# Full_Schematic.net
KiCad netlist of a schematic drawn in EAGLE
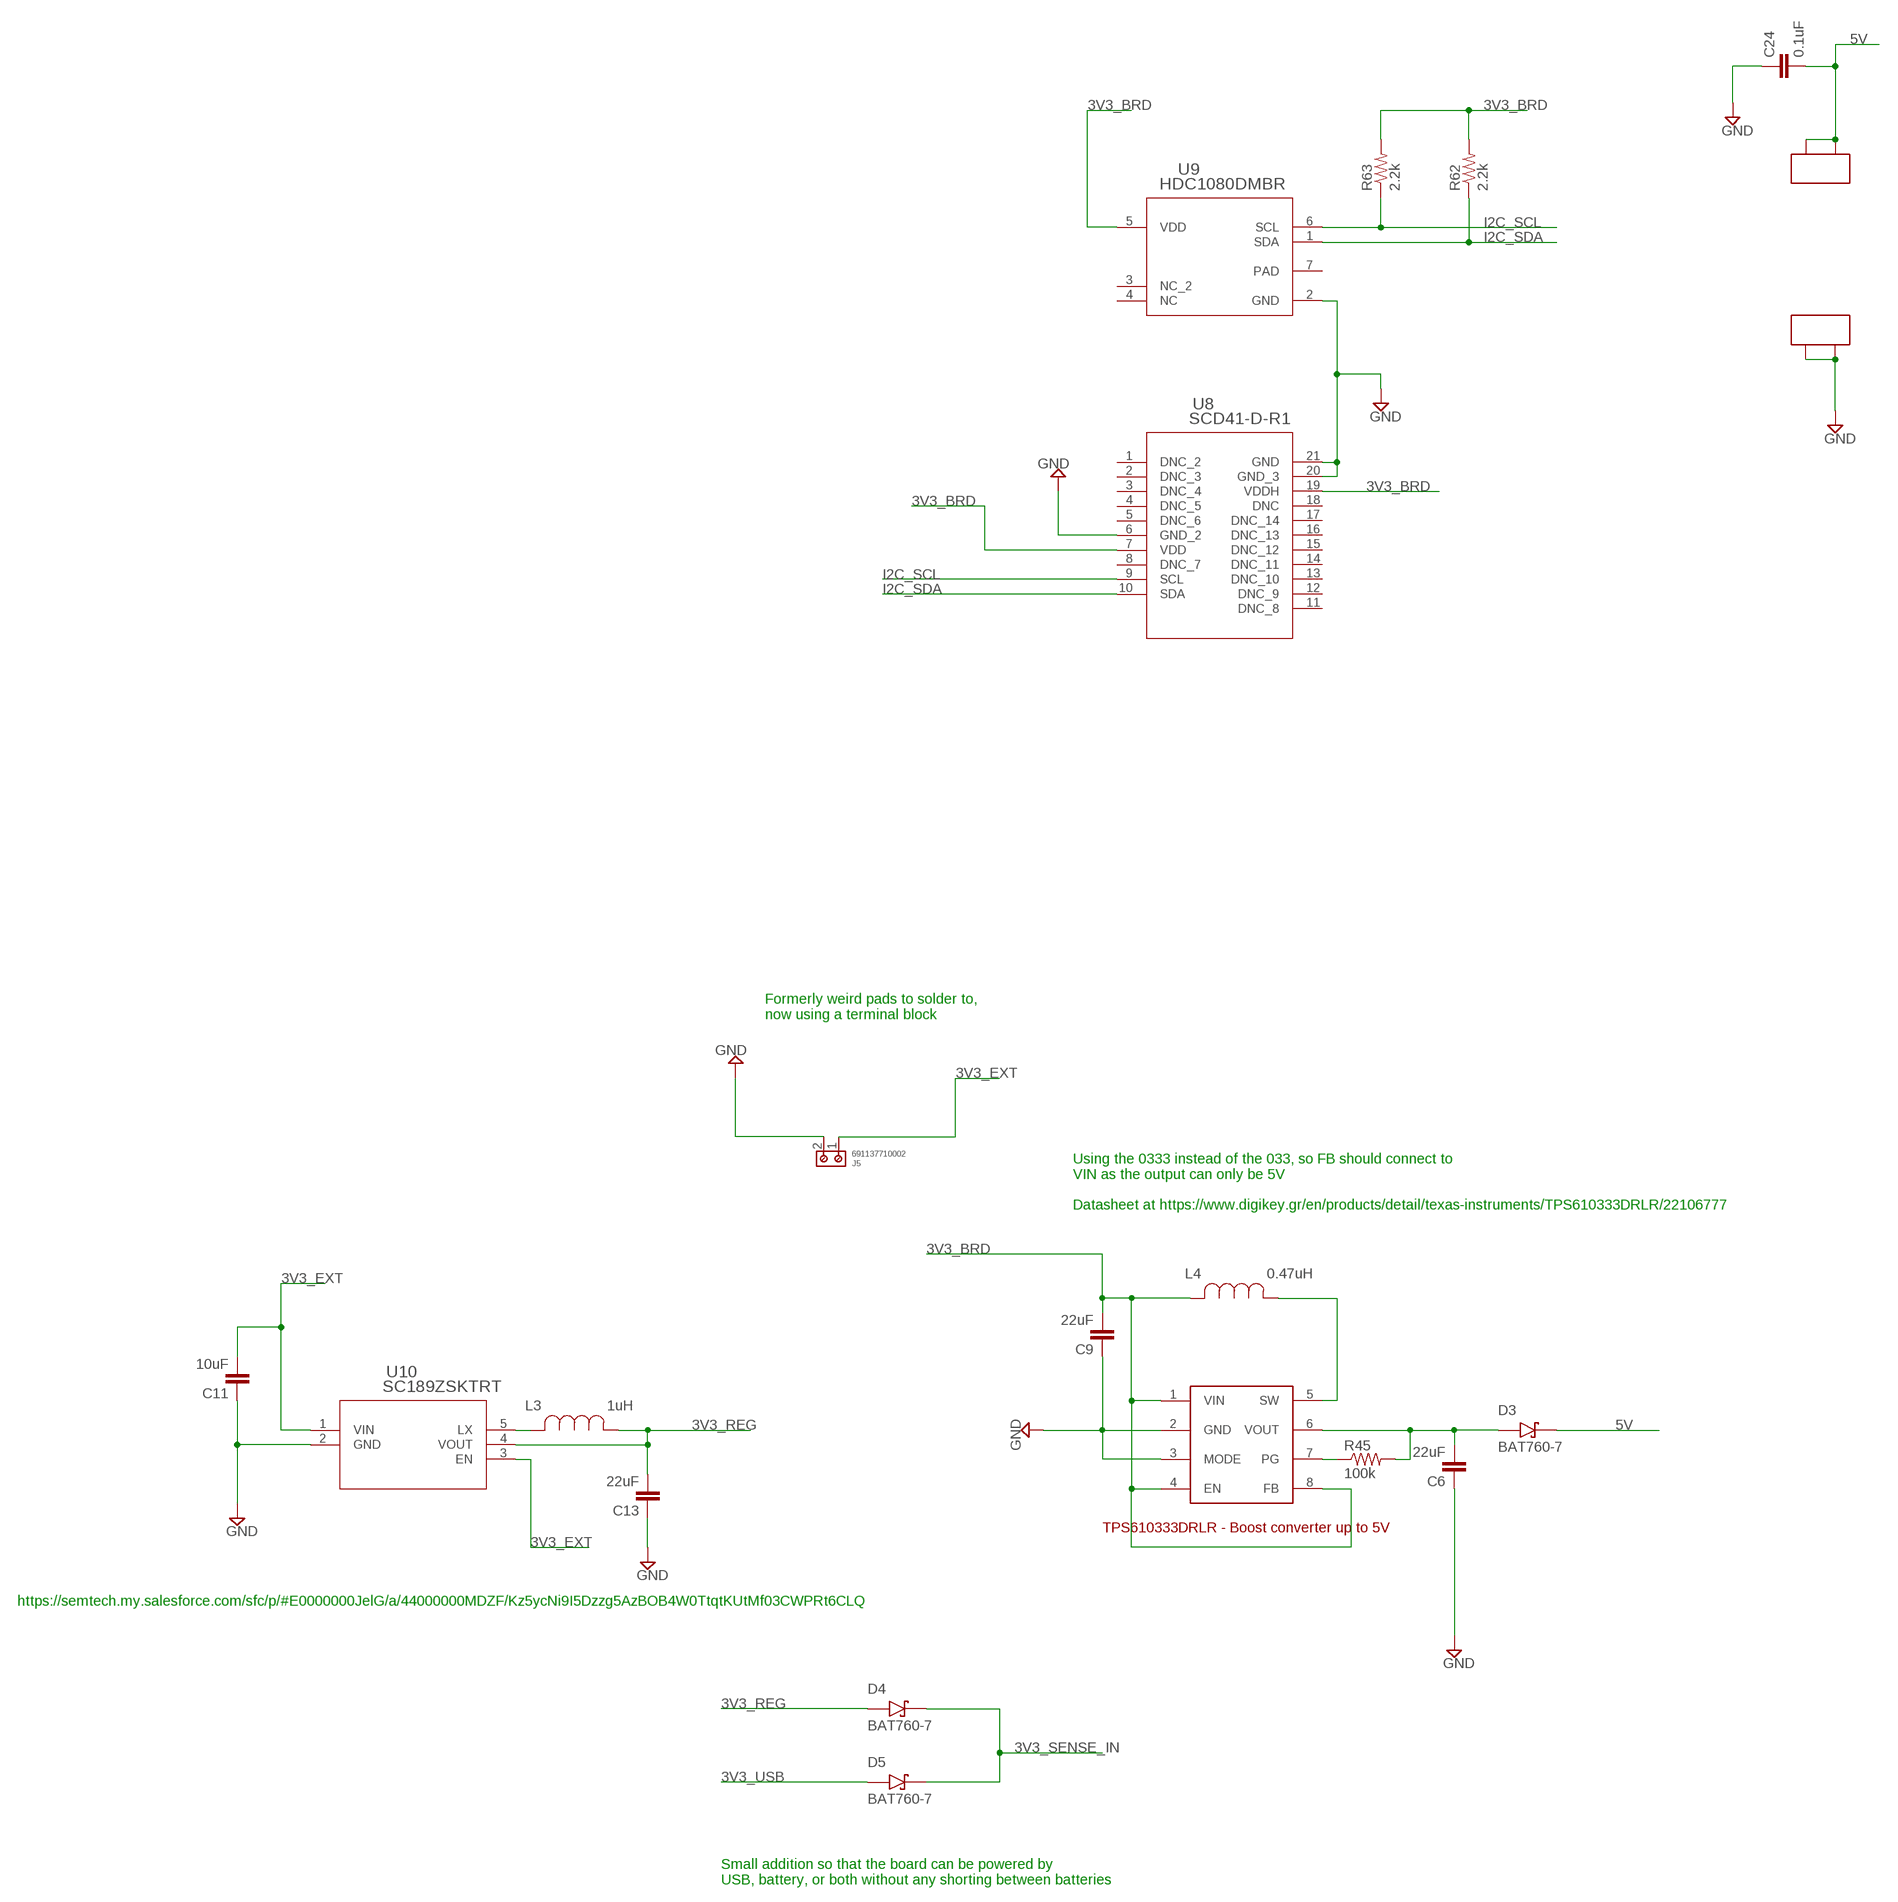
[diagram p0: schematic, sheet 1, part 1 of 3]
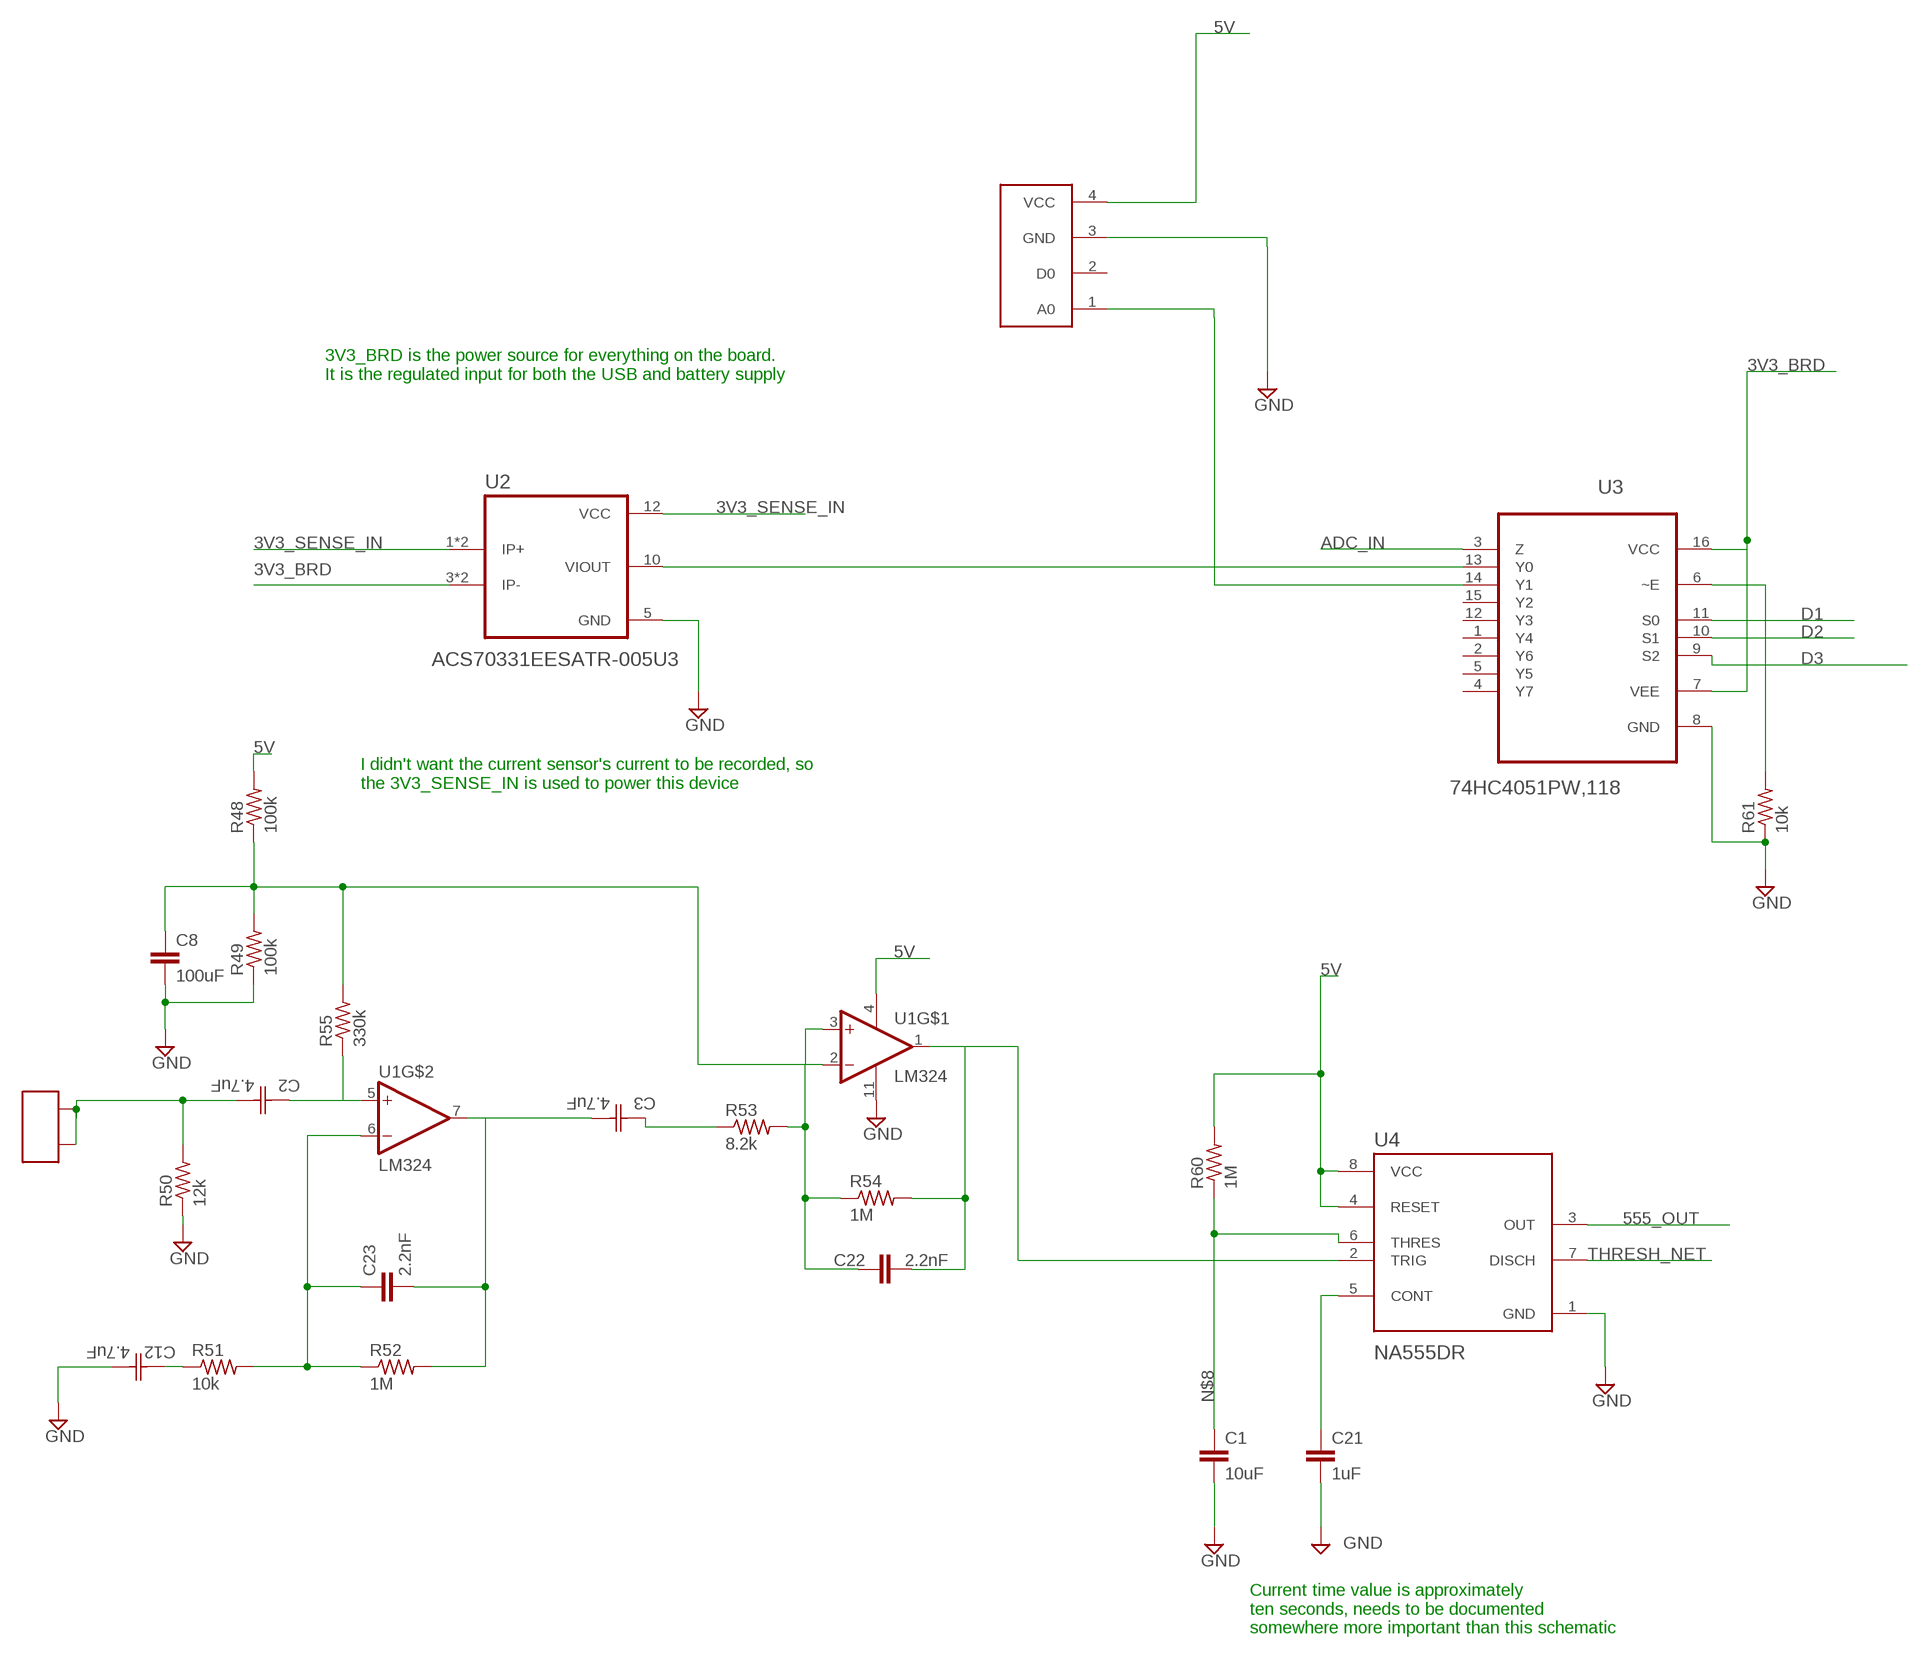
[diagram p1: schematic, sheet 1, part 2 of 3]
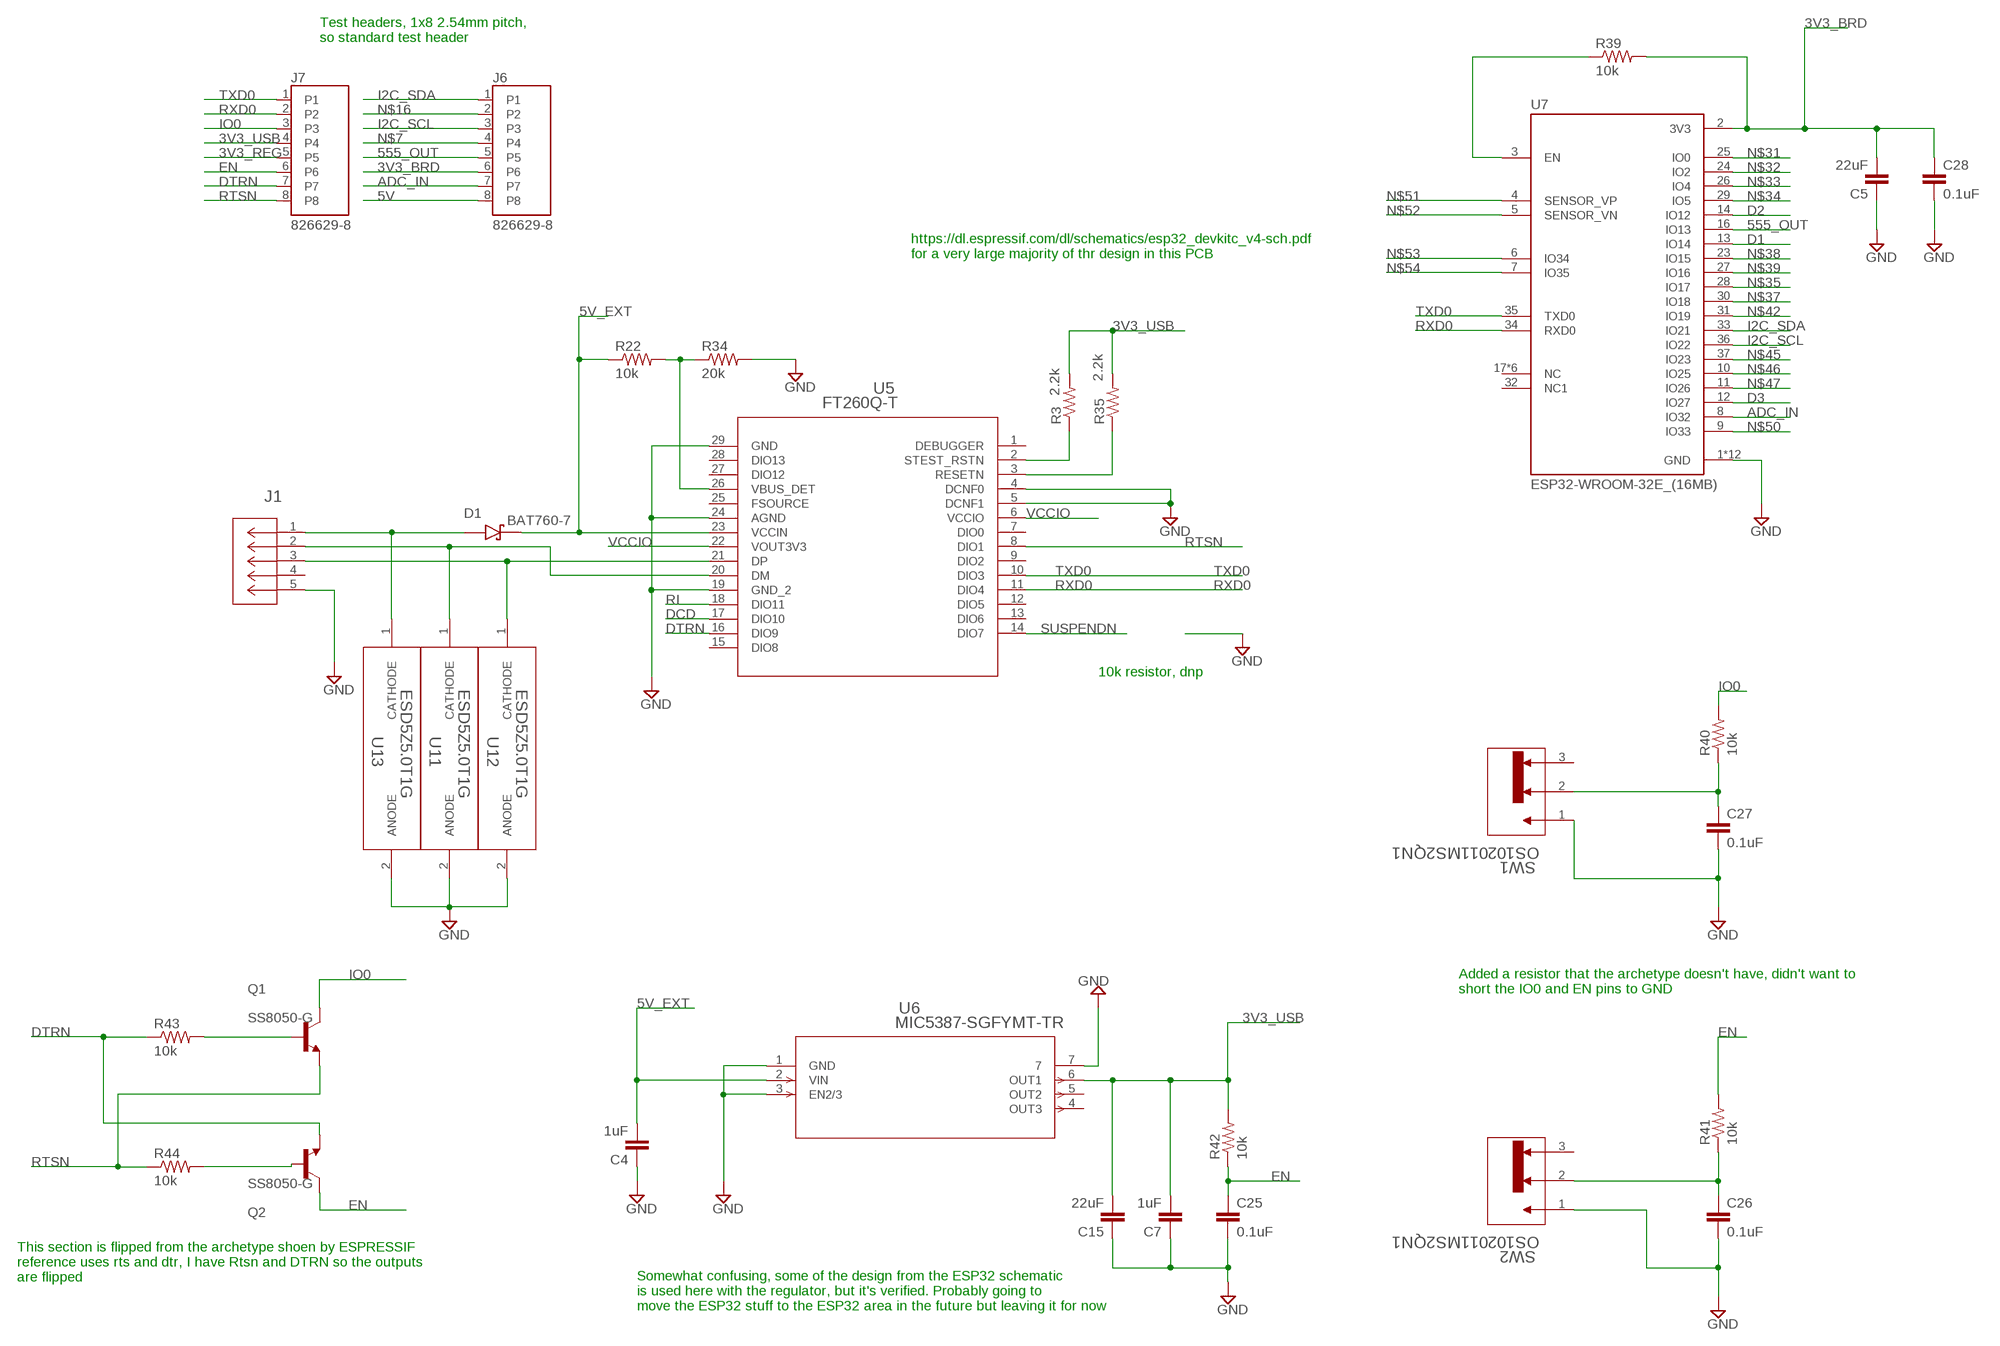
[diagram p2: schematic, sheet 1, part 3 of 3]

(export (version "E")
  (design (tool "Eeschema 10.0.6"))
  (components
    (comp (ref "C1")
      (value "10uF")
      (footprint "eagle-import:C0603")
      (libsource (lib "eagle-import") (part "C-EUC0603"))
    )
    (comp (ref "C2")
      (value "4.7uF")
      (footprint "eagle-import:CAP_WCAP-ATG5_5X11_WRE")
      (fields
        (field (name "MANUFACTURER_PART_NUMBER") "860020472001")
        (field (name "COPYRIGHT") "Copyright (C) 2024 Ultra Librarian. All rights reserved.")
      )
      (libsource (lib "eagle-import") (part "860020472001"))
    )
    (comp (ref "C3")
      (value "4.7uF")
      (footprint "eagle-import:CAP_WCAP-ATG5_5X11_WRE")
      (fields
        (field (name "MANUFACTURER_PART_NUMBER") "860020472001")
        (field (name "COPYRIGHT") "Copyright (C) 2024 Ultra Librarian. All rights reserved.")
      )
      (libsource (lib "eagle-import") (part "860020472001"))
    )
    (comp (ref "C4")
      (value "1uF")
      (footprint "eagle-import:C0603")
      (libsource (lib "eagle-import") (part "C-EUC0603"))
    )
    (comp (ref "C5")
      (value "22uF")
      (footprint "eagle-import:C0603")
      (libsource (lib "eagle-import") (part "C-EUC0603"))
    )
    (comp (ref "C6")
      (value "22uF")
      (footprint "eagle-import:C0603")
      (libsource (lib "eagle-import") (part "C-EUC0603"))
    )
    (comp (ref "C7")
      (value "1uF")
      (footprint "eagle-import:C0603")
      (libsource (lib "eagle-import") (part "C-EUC0603"))
    )
    (comp (ref "C8")
      (value "100uF")
      (footprint "eagle-import:C1206")
      (libsource (lib "eagle-import") (part "C-EUC1206"))
    )
    (comp (ref "C9")
      (value "22uF")
      (footprint "eagle-import:C0603")
      (libsource (lib "eagle-import") (part "C-EUC0603"))
    )
    (comp (ref "C11")
      (value "10uF")
      (footprint "eagle-import:C0603")
      (libsource (lib "eagle-import") (part "C-EUC0603"))
    )
    (comp (ref "C12")
      (value "4.7uF")
      (footprint "eagle-import:CAP_WCAP-ATG5_5X11_WRE")
      (fields
        (field (name "MANUFACTURER_PART_NUMBER") "860020472001")
        (field (name "COPYRIGHT") "Copyright (C) 2024 Ultra Librarian. All rights reserved.")
      )
      (libsource (lib "eagle-import") (part "860020472001"))
    )
    (comp (ref "C13")
      (value "22uF")
      (footprint "eagle-import:C0603")
      (libsource (lib "eagle-import") (part "C-EUC0603"))
    )
    (comp (ref "C15")
      (value "22uF")
      (footprint "eagle-import:C0603")
      (libsource (lib "eagle-import") (part "C-EUC0603"))
    )
    (comp (ref "C21")
      (value "1uF")
      (footprint "eagle-import:C0402")
      (libsource (lib "eagle-import") (part "C-EUC0402"))
    )
    (comp (ref "C22")
      (value "2.2nF")
      (footprint "eagle-import:C0402")
      (libsource (lib "eagle-import") (part "C-EUC0402"))
    )
    (comp (ref "C23")
      (value "2.2nF")
      (footprint "eagle-import:C0402")
      (libsource (lib "eagle-import") (part "C-EUC0402"))
    )
    (comp (ref "C24")
      (value "0.1uF")
      (footprint "eagle-import:C0402")
      (libsource (lib "eagle-import") (part "C-EUC0402"))
    )
    (comp (ref "C25")
      (value "0.1uF")
      (footprint "eagle-import:C0402")
      (libsource (lib "eagle-import") (part "C-EUC0402"))
    )
    (comp (ref "C26")
      (value "0.1uF")
      (footprint "eagle-import:C0402")
      (libsource (lib "eagle-import") (part "C-EUC0402"))
    )
    (comp (ref "C27")
      (value "0.1uF")
      (footprint "eagle-import:C0402")
      (libsource (lib "eagle-import") (part "C-EUC0402"))
    )
    (comp (ref "C28")
      (value "0.1uF")
      (footprint "eagle-import:C0402")
      (libsource (lib "eagle-import") (part "C-EUC0402"))
    )
    (comp (ref "D1")
      (value "BAT760-7")
      (footprint "eagle-import:SOD2513X120N")
      (fields (field (name "MANUFACTURER") "DIODES"))
      (libsource (lib "eagle-import") (part "BAT760-7"))
    )
    (comp (ref "D3")
      (value "BAT760-7")
      (footprint "eagle-import:SOD2513X120N")
      (fields (field (name "MANUFACTURER") "DIODES"))
      (libsource (lib "eagle-import") (part "BAT760-7"))
    )
    (comp (ref "D4")
      (value "BAT760-7")
      (footprint "eagle-import:SOD2513X120N")
      (fields (field (name "MANUFACTURER") "DIODES"))
      (libsource (lib "eagle-import") (part "BAT760-7"))
    )
    (comp (ref "D5")
      (value "BAT760-7")
      (footprint "eagle-import:SOD2513X120N")
      (fields (field (name "MANUFACTURER") "DIODES"))
      (libsource (lib "eagle-import") (part "BAT760-7"))
    )
    (comp (ref "J1")
      (value "10118193-0001LF")
      (footprint "eagle-import:CONN_10118193-0001LF_AMP")
      (fields (field (name "COPYRIGHT") "Copyright (C) 2024 Ultra Librarian. All rights reserved."))
      (libsource (lib "eagle-import") (part "10118193-0001LF"))
    )
    (comp (ref "J5")
      (value "691137710002")
      (footprint "eagle-import:691137710002")
      (fields (field (name "MF") "Wurth Electronics"))
      (libsource (lib "eagle-import") (part "691137710002"))
    )
    (comp (ref "J6")
      (value "826629-8")
      (footprint "eagle-import:TE_826629-8")
      (fields (field (name "MF") "TE Connectivity"))
      (libsource (lib "eagle-import") (part "826629-8"))
    )
    (comp (ref "J7")
      (value "826629-8")
      (footprint "eagle-import:TE_826629-8")
      (fields (field (name "MF") "TE Connectivity"))
      (libsource (lib "eagle-import") (part "826629-8"))
    )
    (comp (ref "L3")
      (value "1uH")
      (footprint "eagle-import:DFE252012P-1R0M=P2")
      (fields
        (field (name "MANUFACTURER_PART_NUMBER") "DFE252012P-1R0M=P2")
        (field (name "COPYRIGHT") "Copyright (C) 2024 Ultra Librarian. All rights reserved.")
      )
      (libsource (lib "eagle-import") (part "DFE252012P-1R0M=P2"))
    )
    (comp (ref "L4")
      (value "0.47uH")
      (footprint "eagle-import:DFE252012P-1R0M=P2")
      (fields
        (field (name "MANUFACTURER_PART_NUMBER") "DFE252012P-1R0M=P2")
        (field (name "COPYRIGHT") "Copyright (C) 2024 Ultra Librarian. All rights reserved.")
      )
      (libsource (lib "eagle-import") (part "DFE252012P-1R0M=P2"))
    )
    (comp (ref "Q1")
      (value "SS8050-G")
      (footprint "eagle-import:TRANS_SS8050-G")
      (fields (field (name "MANUFACTURER") "Comchip"))
      (libsource (lib "eagle-import") (part "SS8050-G"))
    )
    (comp (ref "Q2")
      (value "SS8050-G")
      (footprint "eagle-import:TRANS_SS8050-G")
      (fields (field (name "MANUFACTURER") "Comchip"))
      (libsource (lib "eagle-import") (part "SS8050-G"))
    )
    (comp (ref "R3")
      (value "2.2k")
      (footprint "eagle-import:R0402")
      (libsource (lib "eagle-import") (part "R-US_R0402"))
    )
    (comp (ref "R22")
      (value "10k")
      (footprint "eagle-import:R0402")
      (libsource (lib "eagle-import") (part "R-US_R0402"))
    )
    (comp (ref "R34")
      (value "20k")
      (footprint "eagle-import:R0402")
      (libsource (lib "eagle-import") (part "R-US_R0402"))
    )
    (comp (ref "R35")
      (value "2.2k")
      (footprint "eagle-import:R0402")
      (libsource (lib "eagle-import") (part "R-US_R0402"))
    )
    (comp (ref "R39")
      (value "10k")
      (footprint "eagle-import:R0402")
      (libsource (lib "eagle-import") (part "R-US_R0402"))
    )
    (comp (ref "R40")
      (value "10k")
      (footprint "eagle-import:R0402")
      (libsource (lib "eagle-import") (part "R-US_R0402"))
    )
    (comp (ref "R41")
      (value "10k")
      (footprint "eagle-import:R0402")
      (libsource (lib "eagle-import") (part "R-US_R0402"))
    )
    (comp (ref "R42")
      (value "10k")
      (footprint "eagle-import:R0402")
      (libsource (lib "eagle-import") (part "R-US_R0402"))
    )
    (comp (ref "R43")
      (value "10k")
      (footprint "eagle-import:R0402")
      (libsource (lib "eagle-import") (part "R-US_R0402"))
    )
    (comp (ref "R44")
      (value "10k")
      (footprint "eagle-import:R0402")
      (libsource (lib "eagle-import") (part "R-US_R0402"))
    )
    (comp (ref "R45")
      (value "100k")
      (footprint "eagle-import:R0402")
      (libsource (lib "eagle-import") (part "R-US_R0402"))
    )
    (comp (ref "R48")
      (value "100k")
      (footprint "eagle-import:R0402")
      (libsource (lib "eagle-import") (part "R-US_R0402"))
    )
    (comp (ref "R49")
      (value "100k")
      (footprint "eagle-import:R0402")
      (libsource (lib "eagle-import") (part "R-US_R0402"))
    )
    (comp (ref "R50")
      (value "12k")
      (footprint "eagle-import:R0402")
      (libsource (lib "eagle-import") (part "R-US_R0402"))
    )
    (comp (ref "R51")
      (value "10k")
      (footprint "eagle-import:R0402")
      (libsource (lib "eagle-import") (part "R-US_R0402"))
    )
    (comp (ref "R52")
      (value "1M")
      (footprint "eagle-import:R0402")
      (libsource (lib "eagle-import") (part "R-US_R0402"))
    )
    (comp (ref "R53")
      (value "8.2k")
      (footprint "eagle-import:R0402")
      (libsource (lib "eagle-import") (part "R-US_R0402"))
    )
    (comp (ref "R54")
      (value "1M")
      (footprint "eagle-import:R0402")
      (libsource (lib "eagle-import") (part "R-US_R0402"))
    )
    (comp (ref "R55")
      (value "330k")
      (footprint "eagle-import:R0402")
      (libsource (lib "eagle-import") (part "R-US_R0402"))
    )
    (comp (ref "R60")
      (value "1M")
      (footprint "eagle-import:R0402")
      (libsource (lib "eagle-import") (part "R-US_R0402"))
    )
    (comp (ref "R61")
      (value "10k")
      (footprint "eagle-import:R0402")
      (libsource (lib "eagle-import") (part "R-US_R0402"))
    )
    (comp (ref "R62")
      (value "2.2k")
      (footprint "eagle-import:R0402")
      (libsource (lib "eagle-import") (part "R-US_R0402"))
    )
    (comp (ref "R63")
      (value "2.2k")
      (footprint "eagle-import:R0402")
      (libsource (lib "eagle-import") (part "R-US_R0402"))
    )
    (comp (ref "SW1")
      (value "OS102011MS2QN1")
      (footprint "eagle-import:SPDT_OS102011_CNK")
      (fields (field (name "COPYRIGHT") "Copyright (C) 2024 Ultra Librarian. All rights reserved."))
      (libsource (lib "eagle-import") (part "OS102011MS2QN1"))
    )
    (comp (ref "SW2")
      (value "OS102011MS2QN1")
      (footprint "eagle-import:SPDT_OS102011_CNK")
      (fields (field (name "COPYRIGHT") "Copyright (C) 2024 Ultra Librarian. All rights reserved."))
      (libsource (lib "eagle-import") (part "OS102011MS2QN1"))
    )
    (comp (ref "U$1")
      (value "2PIN_HEADER")
      (footprint "eagle-import:2PIN_HEADER")
      (libsource (lib "eagle-import") (part "2PIN_HEADER"))
    )
    (comp (ref "U$2")
      (value "2PIN_HEADER")
      (footprint "eagle-import:2PIN_HEADER")
      (libsource (lib "eagle-import") (part "2PIN_HEADER"))
    )
    (comp (ref "U$3")
      (value "MQ_7")
      (footprint "eagle-import:MQ-7")
      (libsource (lib "eagle-import") (part "MQ_7"))
    )
    (comp (ref "U$4")
      (value "TPS610333DRLR")
      (footprint "eagle-import:TPS610333DRLR")
      (libsource (lib "eagle-import") (part "TPS610333DRLR"))
    )
    (comp (ref "U$5")
      (value "2PIN_HEADER")
      (footprint "eagle-import:2PIN_HEADER")
      (libsource (lib "eagle-import") (part "2PIN_HEADER"))
    )
    (comp (ref "U1")
      (value "LM324")
      (footprint "eagle-import:SOIC127P600X175-14N")
      (fields (field (name "MF") "Intersil") (field (name "MP") "LM324.."))
      (libsource (lib "eagle-import") (part "LM324"))
    )
    (comp (ref "U2")
      (value "ACS70331EESATR-005U3")
      (footprint "eagle-import:ALLEGRO_ACS70331EESATR-005U3")
      (fields (field (name "MF") "Allegro MicroSystems LLC"))
      (libsource (lib "eagle-import") (part "ACS70331EESATR-005U3"))
    )
    (comp (ref "U3")
      (value "74HC4051PW,118")
      (footprint "eagle-import:SOP65P640X110-16N")
      (fields (field (name "MF") "Nexperia USA Inc."))
      (libsource (lib "eagle-import") (part "74HC4051PW,118"))
    )
    (comp (ref "U4")
      (value "NA555DR")
      (footprint "eagle-import:SOIC127P599X175-8N")
      (fields (field (name "MANUFACTURER") "Texas Instruments"))
      (libsource (lib "eagle-import") (part "NA555DR"))
    )
    (comp (ref "U5")
      (value "FT260Q-T")
      (footprint "eagle-import:WQFN-28_FTD")
      (fields (field (name "COPYRIGHT") "Copyright (C) 2024 Ultra Librarian. All rights reserved."))
      (libsource (lib "eagle-import") (part "FT260Q-T"))
    )
    (comp (ref "U6")
      (value "MIC5387-SGFYMT-TR")
      (footprint "eagle-import:MLF-6_MT_MCH")
      (fields (field (name "COPYRIGHT") "Copyright (C) 2024 Ultra Librarian. All rights reserved."))
      (libsource (lib "eagle-import") (part "MIC5387-SGFYMT-TR"))
    )
    (comp (ref "U7")
      (value "ESP32-WROOM-32E_(16MB)")
      (footprint "eagle-import:XCVR_ESP32-WROOM-32E_(16MB)")
      (fields (field (name "MF") "Espressif Systems") (field (name "MP") "ESP32-WROOM-32E (16MB)"))
      (libsource (lib "eagle-import") (part "ESP32-WROOM-32E_(16MB)"))
    )
    (comp (ref "U8")
      (value "SCD41-D-R1")
      (footprint "eagle-import:SCD41-D-R1_SEN")
      (fields (field (name "COPYRIGHT") "Copyright (C) 2024 Ultra Librarian. All rights reserved."))
      (libsource (lib "eagle-import") (part "SCD41-D-R1"))
    )
    (comp (ref "U9")
      (value "HDC1080DMBR")
      (footprint "eagle-import:DMB0006A")
      (fields (field (name "COPYRIGHT") "Copyright (C) 2024 Ultra Librarian. All rights reserved."))
      (libsource (lib "eagle-import") (part "HDC1080DMBR"))
    )
    (comp (ref "U10")
      (value "SC189ZSKTRT")
      (footprint "eagle-import:SOT23-5-SC189_SEM")
      (fields (field (name "COPYRIGHT") "Copyright (C) 2024 Ultra Librarian. All rights reserved."))
      (libsource (lib "eagle-import") (part "SC189ZSKTRT"))
    )
    (comp (ref "U11")
      (value "ESD5Z5.0T1G")
      (footprint "eagle-import:SOD-523_0P9X1P3_ONS")
      (fields (field (name "COPYRIGHT") "Copyright (C) 2024 Ultra Librarian. All rights reserved."))
      (libsource (lib "eagle-import") (part "ESD5Z5.0T1G"))
    )
    (comp (ref "U12")
      (value "ESD5Z5.0T1G")
      (footprint "eagle-import:SOD-523_0P9X1P3_ONS")
      (fields (field (name "COPYRIGHT") "Copyright (C) 2024 Ultra Librarian. All rights reserved."))
      (libsource (lib "eagle-import") (part "ESD5Z5.0T1G"))
    )
    (comp (ref "U13")
      (value "ESD5Z5.0T1G")
      (footprint "eagle-import:SOD-523_0P9X1P3_ONS")
      (fields (field (name "COPYRIGHT") "Copyright (C) 2024 Ultra Librarian. All rights reserved."))
      (libsource (lib "eagle-import") (part "ESD5Z5.0T1G"))
    )
  )
  (nets
    (net (code "1") (name "/3V3_BRD") (class "Default")
      (node (ref "C28") (pin "1") (pinfunction "1_1") (pintype "passive"))
      (node (ref "C5") (pin "2") (pinfunction "2_2") (pintype "passive"))
      (node (ref "C9") (pin "2") (pinfunction "2_2") (pintype "passive"))
      (node (ref "J6") (pin "6") (pinfunction "P6_6") (pintype "passive"))
      (node (ref "L4") (pin "2") (pinfunction "2_2") (pintype "passive"))
      (node (ref "R39") (pin "2") (pinfunction "2_2") (pintype "passive"))
      (node (ref "R62") (pin "2") (pinfunction "2_2") (pintype "passive"))
      (node (ref "R63") (pin "2") (pinfunction "2_2") (pintype "passive"))
      (node (ref "U$4") (pin "1") (pinfunction "VIN_1") (pintype "bidirectional"))
      (node (ref "U$4") (pin "4") (pinfunction "EN_4") (pintype "bidirectional"))
      (node (ref "U$4") (pin "8") (pinfunction "FB_8") (pintype "bidirectional"))
      (node (ref "U2") (pin "3") (pinfunction "IP-_3") (pintype "input"))
      (node (ref "U2") (pin "4") (pinfunction "IP-_4") (pintype "input"))
      (node (ref "U3") (pin "16") (pinfunction "VCC_16") (pintype "power_in"))
      (node (ref "U3") (pin "7") (pinfunction "VEE_7") (pintype "power_in"))
      (node (ref "U7") (pin "2") (pinfunction "3V3_2") (pintype "power_in"))
      (node (ref "U8") (pin "19") (pinfunction "VDDH_19") (pintype "power_in"))
      (node (ref "U8") (pin "7") (pinfunction "VDD_7") (pintype "power_in"))
      (node (ref "U9") (pin "5") (pinfunction "VDD_5") (pintype "power_in"))
    )
    (net (code "2") (name "/3V3_EXT") (class "Default")
      (node (ref "C11") (pin "2") (pinfunction "2_2") (pintype "passive"))
      (node (ref "J5") (pin "1") (pinfunction "1_1") (pintype "passive"))
      (node (ref "U10") (pin "1") (pinfunction "VIN_1") (pintype "power_in"))
      (node (ref "U10") (pin "3") (pinfunction "EN_3") (pintype "passive"))
    )
    (net (code "3") (name "/3V3_REG") (class "Default")
      (node (ref "C13") (pin "2") (pinfunction "2_2") (pintype "passive"))
      (node (ref "D4") (pin "A") (pinfunction "A_A") (pintype "passive"))
      (node (ref "J7") (pin "5") (pinfunction "P5_5") (pintype "passive"))
      (node (ref "L3") (pin "1") (pinfunction "1_1") (pintype "passive"))
      (node (ref "U10") (pin "4") (pinfunction "VOUT_4") (pintype "output"))
    )
    (net (code "4") (name "/3V3_SENSE_IN") (class "Default")
      (node (ref "D4") (pin "C") (pinfunction "K_C") (pintype "passive"))
      (node (ref "D5") (pin "C") (pinfunction "K_C") (pintype "passive"))
      (node (ref "U2") (pin "1") (pinfunction "IP+_1") (pintype "input"))
      (node (ref "U2") (pin "12") (pinfunction "VCC_12") (pintype "power_in"))
      (node (ref "U2") (pin "2") (pinfunction "IP+_2") (pintype "input"))
    )
    (net (code "5") (name "/3V3_USB") (class "Default")
      (node (ref "C15") (pin "2") (pinfunction "2_2") (pintype "passive"))
      (node (ref "C7") (pin "2") (pinfunction "2_2") (pintype "passive"))
      (node (ref "D5") (pin "A") (pinfunction "A_A") (pintype "passive"))
      (node (ref "J7") (pin "4") (pinfunction "P4_4") (pintype "passive"))
      (node (ref "R3") (pin "2") (pinfunction "2_2") (pintype "passive"))
      (node (ref "R35") (pin "2") (pinfunction "2_2") (pintype "passive"))
      (node (ref "R42") (pin "2") (pinfunction "2_2") (pintype "passive"))
      (node (ref "U6") (pin "6") (pinfunction "OUT1_6") (pintype "output"))
    )
    (net (code "6") (name "/5V") (class "Default")
      (node (ref "C24") (pin "2") (pinfunction "2_2") (pintype "passive"))
      (node (ref "D3") (pin "C") (pinfunction "K_C") (pintype "passive"))
      (node (ref "J6") (pin "8") (pinfunction "P8_8") (pintype "passive"))
      (node (ref "R48") (pin "2") (pinfunction "2_2") (pintype "passive"))
      (node (ref "R60") (pin "2") (pinfunction "2_2") (pintype "passive"))
      (node (ref "U$2") (pin "1") (pinfunction "1_1") (pintype "passive"))
      (node (ref "U$2") (pin "2") (pinfunction "2_2") (pintype "passive"))
      (node (ref "U$3") (pin "4") (pinfunction "VCC_4") (pintype "bidirectional"))
      (node (ref "U1") (pin "4") (pinfunction "VCC+_4") (pintype "power_in"))
      (node (ref "U4") (pin "4") (pinfunction "RESET_4") (pintype "input"))
      (node (ref "U4") (pin "8") (pinfunction "VCC_8") (pintype "power_in"))
    )
    (net (code "7") (name "/5V_EXT") (class "Default")
      (node (ref "C4") (pin "2") (pinfunction "2_2") (pintype "passive"))
      (node (ref "D1") (pin "C") (pinfunction "K_C") (pintype "passive"))
      (node (ref "R22") (pin "1") (pinfunction "1_1") (pintype "passive"))
      (node (ref "U5") (pin "23") (pinfunction "VCCIN_23") (pintype "power_in"))
      (node (ref "U6") (pin "2") (pinfunction "VIN_2") (pintype "input"))
    )
    (net (code "8") (name "/555_OUT") (class "Default")
      (node (ref "J6") (pin "5") (pinfunction "P5_5") (pintype "passive"))
      (node (ref "U4") (pin "3") (pinfunction "OUT_3") (pintype "output"))
      (node (ref "U7") (pin "16") (pinfunction "IO13_16") (pintype "bidirectional"))
    )
    (net (code "9") (name "/ADC_IN") (class "Default")
      (node (ref "J6") (pin "7") (pinfunction "P7_7") (pintype "passive"))
      (node (ref "U3") (pin "3") (pinfunction "Z_3") (pintype "bidirectional"))
      (node (ref "U7") (pin "8") (pinfunction "IO32_8") (pintype "bidirectional"))
    )
    (net (code "10") (name "/D1") (class "Default")
      (node (ref "U3") (pin "11") (pinfunction "S0_11") (pintype "input"))
      (node (ref "U7") (pin "13") (pinfunction "IO14_13") (pintype "bidirectional"))
    )
    (net (code "11") (name "/D2") (class "Default")
      (node (ref "U3") (pin "10") (pinfunction "S1_10") (pintype "input"))
      (node (ref "U7") (pin "14") (pinfunction "IO12_14") (pintype "bidirectional"))
    )
    (net (code "12") (name "/D3") (class "Default")
      (node (ref "U3") (pin "9") (pinfunction "S2_9") (pintype "input"))
      (node (ref "U7") (pin "12") (pinfunction "IO27_12") (pintype "bidirectional"))
    )
    (net (code "13") (name "/DCD") (class "Default")
      (node (ref "U5") (pin "17") (pinfunction "DIO10_17") (pintype "bidirectional"))
    )
    (net (code "14") (name "/DTRN") (class "Default")
      (node (ref "J7") (pin "7") (pinfunction "P7_7") (pintype "passive"))
      (node (ref "Q2") (pin "2") (pinfunction "E_2") (pintype "passive"))
      (node (ref "R43") (pin "1") (pinfunction "1_1") (pintype "passive"))
      (node (ref "U5") (pin "16") (pinfunction "DIO9_16") (pintype "bidirectional"))
    )
    (net (code "15") (name "/EN") (class "Default")
      (node (ref "C25") (pin "1") (pinfunction "1_1") (pintype "passive"))
      (node (ref "J7") (pin "6") (pinfunction "P6_6") (pintype "passive"))
      (node (ref "Q2") (pin "3") (pinfunction "C_3") (pintype "passive"))
      (node (ref "R41") (pin "2") (pinfunction "2_2") (pintype "passive"))
      (node (ref "R42") (pin "1") (pinfunction "1_1") (pintype "passive"))
    )
    (net (code "16") (name "/FSOURCE") (class "Default")
      (node (ref "U5") (pin "25") (pinfunction "FSOURCE_25") (pintype "power_in"))
    )
    (net (code "17") (name "/I2C_SCL") (class "Default")
      (node (ref "J6") (pin "3") (pinfunction "P3_3") (pintype "passive"))
      (node (ref "R63") (pin "1") (pinfunction "1_1") (pintype "passive"))
      (node (ref "U7") (pin "36") (pinfunction "IO22_36") (pintype "bidirectional"))
      (node (ref "U8") (pin "9") (pinfunction "SCL_9") (pintype "input"))
      (node (ref "U9") (pin "6") (pinfunction "SCL_6") (pintype "open_collector"))
    )
    (net (code "18") (name "/I2C_SDA") (class "Default")
      (node (ref "J6") (pin "1") (pinfunction "P1_1") (pintype "passive"))
      (node (ref "R62") (pin "1") (pinfunction "1_1") (pintype "passive"))
      (node (ref "U7") (pin "33") (pinfunction "IO21_33") (pintype "bidirectional"))
      (node (ref "U8") (pin "10") (pinfunction "SDA_10") (pintype "bidirectional"))
      (node (ref "U9") (pin "1") (pinfunction "SDA_1") (pintype "bidirectional"))
    )
    (net (code "19") (name "/IO0") (class "Default")
      (node (ref "J7") (pin "3") (pinfunction "P3_3") (pintype "passive"))
      (node (ref "Q1") (pin "3") (pinfunction "C_3") (pintype "passive"))
      (node (ref "R40") (pin "2") (pinfunction "2_2") (pintype "passive"))
    )
    (net (code "20") (name "/N$7") (class "Default")
      (node (ref "J6") (pin "4") (pinfunction "P4_4") (pintype "passive"))
      (node (ref "U2") (pin "10") (pinfunction "VIOUT_10") (pintype "output"))
      (node (ref "U3") (pin "13") (pinfunction "Y0_13") (pintype "bidirectional"))
    )
    (net (code "21") (name "/N$8") (class "Default")
      (node (ref "C1") (pin "1") (pinfunction "1_1") (pintype "passive"))
      (node (ref "R60") (pin "1") (pinfunction "1_1") (pintype "passive"))
      (node (ref "U4") (pin "6") (pinfunction "THRES_6") (pintype "input"))
    )
    (net (code "22") (name "/N$16") (class "Default")
      (node (ref "J6") (pin "2") (pinfunction "P2_2") (pintype "passive"))
      (node (ref "U$3") (pin "1") (pinfunction "A0_1") (pintype "bidirectional"))
      (node (ref "U3") (pin "14") (pinfunction "Y1_14") (pintype "bidirectional"))
    )
    (net (code "23") (name "/N$31") (class "Default")
      (node (ref "U7") (pin "25") (pinfunction "IO0_25") (pintype "bidirectional"))
    )
    (net (code "24") (name "/N$32") (class "Default")
      (node (ref "U7") (pin "24") (pinfunction "IO2_24") (pintype "bidirectional"))
    )
    (net (code "25") (name "/N$33") (class "Default")
      (node (ref "U7") (pin "26") (pinfunction "IO4_26") (pintype "bidirectional"))
    )
    (net (code "26") (name "/N$34") (class "Default")
      (node (ref "U7") (pin "29") (pinfunction "IO5_29") (pintype "bidirectional"))
    )
    (net (code "27") (name "/N$35") (class "Default")
      (node (ref "U7") (pin "28") (pinfunction "IO17_28") (pintype "bidirectional"))
    )
    (net (code "28") (name "/N$37") (class "Default")
      (node (ref "U7") (pin "30") (pinfunction "IO18_30") (pintype "bidirectional"))
    )
    (net (code "29") (name "/N$38") (class "Default")
      (node (ref "U7") (pin "23") (pinfunction "IO15_23") (pintype "bidirectional"))
    )
    (net (code "30") (name "/N$39") (class "Default")
      (node (ref "U7") (pin "27") (pinfunction "IO16_27") (pintype "bidirectional"))
    )
    (net (code "31") (name "/N$42") (class "Default")
      (node (ref "U7") (pin "31") (pinfunction "IO19_31") (pintype "bidirectional"))
    )
    (net (code "32") (name "/N$45") (class "Default")
      (node (ref "U7") (pin "37") (pinfunction "IO23_37") (pintype "bidirectional"))
    )
    (net (code "33") (name "/N$46") (class "Default")
      (node (ref "U7") (pin "10") (pinfunction "IO25_10") (pintype "bidirectional"))
    )
    (net (code "34") (name "/N$47") (class "Default")
      (node (ref "U7") (pin "11") (pinfunction "IO26_11") (pintype "bidirectional"))
    )
    (net (code "35") (name "/N$50") (class "Default")
      (node (ref "U7") (pin "9") (pinfunction "IO33_9") (pintype "bidirectional"))
    )
    (net (code "36") (name "/N$51") (class "Default")
      (node (ref "U7") (pin "4") (pinfunction "SENSOR_VP_4") (pintype "input"))
    )
    (net (code "37") (name "/N$52") (class "Default")
      (node (ref "U7") (pin "5") (pinfunction "SENSOR_VN_5") (pintype "input"))
    )
    (net (code "38") (name "/N$53") (class "Default")
      (node (ref "U7") (pin "6") (pinfunction "IO34_6") (pintype "input"))
    )
    (net (code "39") (name "/N$54") (class "Default")
      (node (ref "U7") (pin "7") (pinfunction "IO35_7") (pintype "input"))
    )
    (net (code "40") (name "/PAD") (class "Default")
      (node (ref "U9") (pin "7") (pinfunction "PAD_7") (pintype "power_in"))
    )
    (net (code "41") (name "/RI") (class "Default")
      (node (ref "U5") (pin "18") (pinfunction "DIO11_18") (pintype "bidirectional"))
    )
    (net (code "42") (name "/RTSN") (class "Default")
      (node (ref "J7") (pin "8") (pinfunction "P8_8") (pintype "passive"))
      (node (ref "Q1") (pin "2") (pinfunction "E_2") (pintype "passive"))
      (node (ref "R44") (pin "1") (pinfunction "1_1") (pintype "passive"))
      (node (ref "U5") (pin "8") (pinfunction "DIO1_8") (pintype "bidirectional"))
    )
    (net (code "43") (name "/RXD0") (class "Default")
      (node (ref "J7") (pin "2") (pinfunction "P2_2") (pintype "passive"))
      (node (ref "U5") (pin "11") (pinfunction "DIO4_11") (pintype "bidirectional"))
      (node (ref "U7") (pin "34") (pinfunction "RXD0_34") (pintype "bidirectional"))
    )
    (net (code "44") (name "/SUSPENDN") (class "Default")
      (node (ref "U5") (pin "14") (pinfunction "DIO7_14") (pintype "bidirectional"))
    )
    (net (code "45") (name "/THRESH_NET") (class "Default")
      (node (ref "C22") (pin "2") (pinfunction "2_2") (pintype "passive"))
      (node (ref "R54") (pin "2") (pinfunction "2_2") (pintype "passive"))
      (node (ref "U1") (pin "1") (pinfunction "OUTPUT1_1") (pintype "output"))
      (node (ref "U4") (pin "2") (pinfunction "TRIG_2") (pintype "input"))
      (node (ref "U4") (pin "7") (pinfunction "DISCH_7") (pintype "output"))
    )
    (net (code "46") (name "/TXD0") (class "Default")
      (node (ref "J7") (pin "1") (pinfunction "P1_1") (pintype "passive"))
      (node (ref "U5") (pin "10") (pinfunction "DIO3_10") (pintype "bidirectional"))
      (node (ref "U7") (pin "35") (pinfunction "TXD0_35") (pintype "bidirectional"))
    )
    (net (code "47") (name "/VCCIO") (class "Default")
      (node (ref "U5") (pin "22") (pinfunction "VOUT3V3_22") (pintype "power_in"))
      (node (ref "U5") (pin "6") (pinfunction "VCCIO_6") (pintype "power_in"))
    )
    (net (code "48") (name "GND") (class "Default")
      (node (ref "C1") (pin "2") (pinfunction "2_2") (pintype "passive"))
      (node (ref "C11") (pin "1") (pinfunction "1_1") (pintype "passive"))
      (node (ref "C12") (pin "2") (pinfunction "2_2") (pintype "passive"))
      (node (ref "C13") (pin "1") (pinfunction "1_1") (pintype "passive"))
      (node (ref "C15") (pin "1") (pinfunction "1_1") (pintype "passive"))
      (node (ref "C21") (pin "2") (pinfunction "2_2") (pintype "passive"))
      (node (ref "C24") (pin "1") (pinfunction "1_1") (pintype "passive"))
      (node (ref "C25") (pin "2") (pinfunction "2_2") (pintype "passive"))
      (node (ref "C26") (pin "2") (pinfunction "2_2") (pintype "passive"))
      (node (ref "C27") (pin "2") (pinfunction "2_2") (pintype "passive"))
      (node (ref "C28") (pin "2") (pinfunction "2_2") (pintype "passive"))
      (node (ref "C4") (pin "1") (pinfunction "1_1") (pintype "passive"))
      (node (ref "C5") (pin "1") (pinfunction "1_1") (pintype "passive"))
      (node (ref "C6") (pin "1") (pinfunction "1_1") (pintype "passive"))
      (node (ref "C7") (pin "1") (pinfunction "1_1") (pintype "passive"))
      (node (ref "C8") (pin "2") (pinfunction "2_2") (pintype "passive"))
      (node (ref "C9") (pin "1") (pinfunction "1_1") (pintype "passive"))
      (node (ref "J1") (pin "5") (pinfunction "5_5") (pintype "passive"))
      (node (ref "J5") (pin "2") (pinfunction "2_2") (pintype "passive"))
      (node (ref "R34") (pin "2") (pinfunction "2_2") (pintype "passive"))
      (node (ref "R49") (pin "1") (pinfunction "1_1") (pintype "passive"))
      (node (ref "R50") (pin "1") (pinfunction "1_1") (pintype "passive"))
      (node (ref "R61") (pin "1") (pinfunction "1_1") (pintype "passive"))
      (node (ref "SW1") (pin "1") (pinfunction "1_1") (pintype "passive"))
      (node (ref "SW2") (pin "1") (pinfunction "1_1") (pintype "passive"))
      (node (ref "U$3") (pin "3") (pinfunction "GND_3") (pintype "bidirectional"))
      (node (ref "U$4") (pin "2") (pinfunction "GND_2") (pintype "bidirectional"))
      (node (ref "U$4") (pin "3") (pinfunction "MODE_3") (pintype "bidirectional"))
      (node (ref "U$5") (pin "1") (pinfunction "1_1") (pintype "passive"))
      (node (ref "U$5") (pin "2") (pinfunction "2_2") (pintype "passive"))
      (node (ref "U1") (pin "11") (pinfunction "VCC-_11") (pintype "power_in"))
      (node (ref "U10") (pin "2") (pinfunction "GND_2") (pintype "passive"))
      (node (ref "U11") (pin "2") (pinfunction "ANODE_2") (pintype "passive"))
      (node (ref "U12") (pin "2") (pinfunction "ANODE_2") (pintype "passive"))
      (node (ref "U13") (pin "2") (pinfunction "ANODE_2") (pintype "passive"))
      (node (ref "U2") (pin "5") (pinfunction "GND_5") (pintype "power_in"))
      (node (ref "U3") (pin "8") (pinfunction "GND_8") (pintype "passive"))
      (node (ref "U4") (pin "1") (pinfunction "GND_1") (pintype "power_in"))
      (node (ref "U5") (pin "19") (pinfunction "GND_2_19") (pintype "passive"))
      (node (ref "U5") (pin "24") (pinfunction "AGND_24") (pintype "passive"))
      (node (ref "U5") (pin "29") (pinfunction "GND_29") (pintype "passive"))
      (node (ref "U5") (pin "4") (pinfunction "DCNF0_4") (pintype "input"))
      (node (ref "U5") (pin "5") (pinfunction "DCNF1_5") (pintype "input"))
      (node (ref "U6") (pin "1") (pinfunction "GND_1") (pintype "power_in"))
      (node (ref "U6") (pin "3") (pinfunction "EN2/3_3") (pintype "input"))
      (node (ref "U6") (pin "7") (pinfunction "7_7") (pintype "passive"))
      (node (ref "U7") (pin "1") (pinfunction "GND_1") (pintype "power_in"))
      (node (ref "U7") (pin "15") (pinfunction "GND_15") (pintype "power_in"))
      (node (ref "U7") (pin "38") (pinfunction "GND_38") (pintype "power_in"))
      (node (ref "U7") (pin "39_1") (pinfunction "GND_39_1") (pintype "power_in"))
      (node (ref "U7") (pin "39_2") (pinfunction "GND_39_2") (pintype "power_in"))
      (node (ref "U7") (pin "39_3") (pinfunction "GND_39_3") (pintype "power_in"))
      (node (ref "U7") (pin "39_4") (pinfunction "GND_39_4") (pintype "power_in"))
      (node (ref "U7") (pin "39_5") (pinfunction "GND_39_5") (pintype "power_in"))
      (node (ref "U7") (pin "39_6") (pinfunction "GND_39_6") (pintype "power_in"))
      (node (ref "U7") (pin "39_7") (pinfunction "GND_39_7") (pintype "power_in"))
      (node (ref "U7") (pin "39_8") (pinfunction "GND_39_8") (pintype "power_in"))
      (node (ref "U7") (pin "39_9") (pinfunction "GND_39_9") (pintype "power_in"))
      (node (ref "U8") (pin "20") (pinfunction "GND_3_20") (pintype "passive"))
      (node (ref "U8") (pin "21") (pinfunction "GND_21") (pintype "passive"))
      (node (ref "U8") (pin "6") (pinfunction "GND_2_6") (pintype "passive"))
      (node (ref "U9") (pin "2") (pinfunction "GND_2") (pintype "power_in"))
    )
    (net (code "49") (name "Net-(C2-Pad2)") (class "Default")
      (node (ref "C2") (pin "2") (pinfunction "2_2") (pintype "passive"))
      (node (ref "R50") (pin "2") (pinfunction "2_2") (pintype "passive"))
      (node (ref "U$1") (pin "1") (pinfunction "1_1") (pintype "passive"))
      (node (ref "U$1") (pin "2") (pinfunction "2_2") (pintype "passive"))
    )
    (net (code "50") (name "Net-(C3-Pad1)") (class "Default")
      (node (ref "C3") (pin "1") (pinfunction "1_1") (pintype "passive"))
      (node (ref "R53") (pin "1") (pinfunction "1_1") (pintype "passive"))
    )
    (net (code "51") (name "Net-(C12-Pad1)") (class "Default")
      (node (ref "C12") (pin "1") (pinfunction "1_1") (pintype "passive"))
      (node (ref "R51") (pin "1") (pinfunction "1_1") (pintype "passive"))
    )
    (net (code "52") (name "Net-(C26-Pad1)") (class "Default")
      (node (ref "C26") (pin "1") (pinfunction "1_1") (pintype "passive"))
      (node (ref "R41") (pin "1") (pinfunction "1_1") (pintype "passive"))
      (node (ref "SW2") (pin "2") (pinfunction "2_2") (pintype "passive"))
    )
    (net (code "53") (name "Net-(C27-Pad1)") (class "Default")
      (node (ref "C27") (pin "1") (pinfunction "1_1") (pintype "passive"))
      (node (ref "R40") (pin "1") (pinfunction "1_1") (pintype "passive"))
      (node (ref "SW1") (pin "2") (pinfunction "2_2") (pintype "passive"))
    )
    (net (code "54") (name "Net-(Q1-B)") (class "Default")
      (node (ref "Q1") (pin "1") (pinfunction "B_1") (pintype "passive"))
      (node (ref "R43") (pin "2") (pinfunction "2_2") (pintype "passive"))
    )
    (net (code "55") (name "Net-(Q2-B)") (class "Default")
      (node (ref "Q2") (pin "1") (pinfunction "B_1") (pintype "passive"))
      (node (ref "R44") (pin "2") (pinfunction "2_2") (pintype "passive"))
    )
    (net (code "56") (name "Net-(U$4-PG)") (class "Default")
      (node (ref "R45") (pin "1") (pinfunction "1_1") (pintype "passive"))
      (node (ref "U$4") (pin "7") (pinfunction "PG_7") (pintype "bidirectional"))
    )
    (net (code "57") (name "Net-(U$4-SW)") (class "Default")
      (node (ref "L4") (pin "1") (pinfunction "1_1") (pintype "passive"))
      (node (ref "U$4") (pin "5") (pinfunction "SW_5") (pintype "bidirectional"))
    )
    (net (code "58") (name "Net-(U$4-VOUT)") (class "Default")
      (node (ref "C6") (pin "2") (pinfunction "2_2") (pintype "passive"))
      (node (ref "D3") (pin "A") (pinfunction "A_A") (pintype "passive"))
      (node (ref "R45") (pin "2") (pinfunction "2_2") (pintype "passive"))
      (node (ref "U$4") (pin "6") (pinfunction "VOUT_6") (pintype "bidirectional"))
    )
    (net (code "59") (name "Net-(U1A-INVERTING_INPUT1)") (class "Default")
      (node (ref "C8") (pin "1") (pinfunction "1_1") (pintype "passive"))
      (node (ref "R48") (pin "1") (pinfunction "1_1") (pintype "passive"))
      (node (ref "R49") (pin "2") (pinfunction "2_2") (pintype "passive"))
      (node (ref "R55") (pin "2") (pinfunction "2_2") (pintype "passive"))
      (node (ref "U1") (pin "2") (pinfunction "INVERTING_INPUT1_2") (pintype "input"))
    )
    (net (code "60") (name "Net-(U1A-NON-INVERTING_INPUT1)") (class "Default")
      (node (ref "C22") (pin "1") (pinfunction "1_1") (pintype "passive"))
      (node (ref "R53") (pin "2") (pinfunction "2_2") (pintype "passive"))
      (node (ref "R54") (pin "1") (pinfunction "1_1") (pintype "passive"))
      (node (ref "U1") (pin "3") (pinfunction "NON-INVERTING_INPUT1_3") (pintype "input"))
    )
    (net (code "61") (name "Net-(U1B-INVERTING_INPUT2)") (class "Default")
      (node (ref "C23") (pin "1") (pinfunction "1_1") (pintype "passive"))
      (node (ref "R51") (pin "2") (pinfunction "2_2") (pintype "passive"))
      (node (ref "R52") (pin "1") (pinfunction "1_1") (pintype "passive"))
      (node (ref "U1") (pin "6") (pinfunction "INVERTING_INPUT2_6") (pintype "input"))
    )
    (net (code "62") (name "Net-(U1B-NON-INVERTING_INPUT2)") (class "Default")
      (node (ref "C2") (pin "1") (pinfunction "1_1") (pintype "passive"))
      (node (ref "R55") (pin "1") (pinfunction "1_1") (pintype "passive"))
      (node (ref "U1") (pin "5") (pinfunction "NON-INVERTING_INPUT2_5") (pintype "input"))
    )
    (net (code "63") (name "Net-(U1B-OUTPUT2)") (class "Default")
      (node (ref "C23") (pin "2") (pinfunction "2_2") (pintype "passive"))
      (node (ref "C3") (pin "2") (pinfunction "2_2") (pintype "passive"))
      (node (ref "R52") (pin "2") (pinfunction "2_2") (pintype "passive"))
      (node (ref "U1") (pin "7") (pinfunction "OUTPUT2_7") (pintype "output"))
    )
    (net (code "64") (name "Net-(U3-~{E})") (class "Default")
      (node (ref "R61") (pin "2") (pinfunction "2_2") (pintype "passive"))
      (node (ref "U3") (pin "6") (pinfunction "~{E}_6") (pintype "input"))
    )
    (net (code "65") (name "Net-(U4-CONT)") (class "Default")
      (node (ref "C21") (pin "1") (pinfunction "1_1") (pintype "passive"))
      (node (ref "U4") (pin "5") (pinfunction "CONT_5") (pintype "bidirectional"))
    )
    (net (code "66") (name "Net-(U5-RESETN)") (class "Default")
      (node (ref "R35") (pin "1") (pinfunction "1_1") (pintype "passive"))
      (node (ref "U5") (pin "3") (pinfunction "RESETN_3") (pintype "input"))
    )
    (net (code "67") (name "Net-(U5-STEST_RSTN)") (class "Default")
      (node (ref "R3") (pin "1") (pinfunction "1_1") (pintype "passive"))
      (node (ref "U5") (pin "2") (pinfunction "STEST_RSTN_2") (pintype "input"))
    )
    (net (code "68") (name "Net-(U5-VBUS_DET)") (class "Default")
      (node (ref "R22") (pin "2") (pinfunction "2_2") (pintype "passive"))
      (node (ref "R34") (pin "1") (pinfunction "1_1") (pintype "passive"))
      (node (ref "U5") (pin "26") (pinfunction "VBUS_DET_26") (pintype "input"))
    )
    (net (code "69") (name "Net-(U7-EN)") (class "Default")
      (node (ref "R39") (pin "1") (pinfunction "1_1") (pintype "passive"))
      (node (ref "U7") (pin "3") (pinfunction "EN_3") (pintype "input"))
    )
    (net (code "70") (name "Net-(U10-LX)") (class "Default")
      (node (ref "L3") (pin "2") (pinfunction "2_2") (pintype "passive"))
      (node (ref "U10") (pin "5") (pinfunction "LX_5") (pintype "passive"))
    )
    (net (code "71") (name "Net-(U11-CATHODE)") (class "Default")
      (node (ref "J1") (pin "2") (pinfunction "2_2") (pintype "passive"))
      (node (ref "U11") (pin "1") (pinfunction "CATHODE_1") (pintype "passive"))
      (node (ref "U5") (pin "20") (pinfunction "DM_20") (pintype "passive"))
    )
    (net (code "72") (name "Net-(U12-CATHODE)") (class "Default")
      (node (ref "J1") (pin "3") (pinfunction "3_3") (pintype "passive"))
      (node (ref "U12") (pin "1") (pinfunction "CATHODE_1") (pintype "passive"))
      (node (ref "U5") (pin "21") (pinfunction "DP_21") (pintype "passive"))
    )
    (net (code "73") (name "Net-(U13-CATHODE)") (class "Default")
      (node (ref "D1") (pin "A") (pinfunction "A_A") (pintype "passive"))
      (node (ref "J1") (pin "1") (pinfunction "1_1") (pintype "passive"))
      (node (ref "U13") (pin "1") (pinfunction "CATHODE_1") (pintype "passive"))
    )
    (net (code "74") (name "unconnected-(J1-Pad4)") (class "Default")
      (node (ref "J1") (pin "4") (pinfunction "4_4") (pintype "passive"))
    )
    (net (code "75") (name "unconnected-(SW1-Pad3)") (class "Default")
      (node (ref "SW1") (pin "3") (pinfunction "3_3") (pintype "passive"))
    )
    (net (code "76") (name "unconnected-(SW2-Pad3)") (class "Default")
      (node (ref "SW2") (pin "3") (pinfunction "3_3") (pintype "passive"))
    )
    (net (code "77") (name "unconnected-(U$3-D0-Pad2)") (class "Default")
      (node (ref "U$3") (pin "2") (pinfunction "D0_2") (pintype "bidirectional"))
    )
    (net (code "78") (name "unconnected-(U3-Y2-Pad15)") (class "Default")
      (node (ref "U3") (pin "15") (pinfunction "Y2_15") (pintype "bidirectional"))
    )
    (net (code "79") (name "unconnected-(U3-Y3-Pad12)") (class "Default")
      (node (ref "U3") (pin "12") (pinfunction "Y3_12") (pintype "bidirectional"))
    )
    (net (code "80") (name "unconnected-(U3-Y4-Pad1)") (class "Default")
      (node (ref "U3") (pin "1") (pinfunction "Y4_1") (pintype "bidirectional"))
    )
    (net (code "81") (name "unconnected-(U3-Y5-Pad5)") (class "Default")
      (node (ref "U3") (pin "5") (pinfunction "Y5_5") (pintype "bidirectional"))
    )
    (net (code "82") (name "unconnected-(U3-Y6-Pad2)") (class "Default")
      (node (ref "U3") (pin "2") (pinfunction "Y6_2") (pintype "bidirectional"))
    )
    (net (code "83") (name "unconnected-(U3-Y7-Pad4)") (class "Default")
      (node (ref "U3") (pin "4") (pinfunction "Y7_4") (pintype "bidirectional"))
    )
    (net (code "84") (name "unconnected-(U5-DEBUGGER-Pad1)") (class "Default")
      (node (ref "U5") (pin "1") (pinfunction "DEBUGGER_1") (pintype "bidirectional"))
    )
    (net (code "85") (name "unconnected-(U5-DIO0-Pad7)") (class "Default")
      (node (ref "U5") (pin "7") (pinfunction "DIO0_7") (pintype "bidirectional"))
    )
    (net (code "86") (name "unconnected-(U5-DIO2-Pad9)") (class "Default")
      (node (ref "U5") (pin "9") (pinfunction "DIO2_9") (pintype "bidirectional"))
    )
    (net (code "87") (name "unconnected-(U5-DIO5-Pad12)") (class "Default")
      (node (ref "U5") (pin "12") (pinfunction "DIO5_12") (pintype "bidirectional"))
    )
    (net (code "88") (name "unconnected-(U5-DIO6-Pad13)") (class "Default")
      (node (ref "U5") (pin "13") (pinfunction "DIO6_13") (pintype "bidirectional"))
    )
    (net (code "89") (name "unconnected-(U5-DIO8-Pad15)") (class "Default")
      (node (ref "U5") (pin "15") (pinfunction "DIO8_15") (pintype "bidirectional"))
    )
    (net (code "90") (name "unconnected-(U5-DIO12-Pad27)") (class "Default")
      (node (ref "U5") (pin "27") (pinfunction "DIO12_27") (pintype "bidirectional"))
    )
    (net (code "91") (name "unconnected-(U5-DIO13-Pad28)") (class "Default")
      (node (ref "U5") (pin "28") (pinfunction "DIO13_28") (pintype "bidirectional"))
    )
    (net (code "92") (name "unconnected-(U6-OUT2-Pad5)") (class "Default")
      (node (ref "U6") (pin "5") (pinfunction "OUT2_5") (pintype "output"))
    )
    (net (code "93") (name "unconnected-(U6-OUT3-Pad4)") (class "Default")
      (node (ref "U6") (pin "4") (pinfunction "OUT3_4") (pintype "output"))
    )
    (net (code "94") (name "unconnected-(U7-NC-Pad17)") (class "Default")
      (node (ref "U7") (pin "17") (pinfunction "NC_17") (pintype "no_connect"))
    )
    (net (code "95") (name "unconnected-(U7-NC-Pad18)") (class "Default")
      (node (ref "U7") (pin "18") (pinfunction "NC_18") (pintype "no_connect"))
    )
    (net (code "96") (name "unconnected-(U7-NC-Pad19)") (class "Default")
      (node (ref "U7") (pin "19") (pinfunction "NC_19") (pintype "no_connect"))
    )
    (net (code "97") (name "unconnected-(U7-NC-Pad20)") (class "Default")
      (node (ref "U7") (pin "20") (pinfunction "NC_20") (pintype "no_connect"))
    )
    (net (code "98") (name "unconnected-(U7-NC-Pad21)") (class "Default")
      (node (ref "U7") (pin "21") (pinfunction "NC_21") (pintype "no_connect"))
    )
    (net (code "99") (name "unconnected-(U7-NC-Pad22)") (class "Default")
      (node (ref "U7") (pin "22") (pinfunction "NC_22") (pintype "no_connect"))
    )
    (net (code "100") (name "unconnected-(U7-NC1-Pad32)") (class "Default")
      (node (ref "U7") (pin "32") (pinfunction "NC1_32") (pintype "no_connect"))
    )
    (net (code "101") (name "unconnected-(U8-DNC-Pad18)") (class "Default")
      (node (ref "U8") (pin "18") (pinfunction "DNC_18") (pintype "no_connect"))
    )
    (net (code "102") (name "unconnected-(U8-DNC_2-Pad1)") (class "Default")
      (node (ref "U8") (pin "1") (pinfunction "DNC_2_1") (pintype "no_connect"))
    )
    (net (code "103") (name "unconnected-(U8-DNC_3-Pad2)") (class "Default")
      (node (ref "U8") (pin "2") (pinfunction "DNC_3_2") (pintype "no_connect"))
    )
    (net (code "104") (name "unconnected-(U8-DNC_4-Pad3)") (class "Default")
      (node (ref "U8") (pin "3") (pinfunction "DNC_4_3") (pintype "no_connect"))
    )
    (net (code "105") (name "unconnected-(U8-DNC_5-Pad4)") (class "Default")
      (node (ref "U8") (pin "4") (pinfunction "DNC_5_4") (pintype "no_connect"))
    )
    (net (code "106") (name "unconnected-(U8-DNC_6-Pad5)") (class "Default")
      (node (ref "U8") (pin "5") (pinfunction "DNC_6_5") (pintype "no_connect"))
    )
    (net (code "107") (name "unconnected-(U8-DNC_7-Pad8)") (class "Default")
      (node (ref "U8") (pin "8") (pinfunction "DNC_7_8") (pintype "no_connect"))
    )
    (net (code "108") (name "unconnected-(U8-DNC_8-Pad11)") (class "Default")
      (node (ref "U8") (pin "11") (pinfunction "DNC_8_11") (pintype "no_connect"))
    )
    (net (code "109") (name "unconnected-(U8-DNC_9-Pad12)") (class "Default")
      (node (ref "U8") (pin "12") (pinfunction "DNC_9_12") (pintype "no_connect"))
    )
    (net (code "110") (name "unconnected-(U8-DNC_10-Pad13)") (class "Default")
      (node (ref "U8") (pin "13") (pinfunction "DNC_10_13") (pintype "no_connect"))
    )
    (net (code "111") (name "unconnected-(U8-DNC_11-Pad14)") (class "Default")
      (node (ref "U8") (pin "14") (pinfunction "DNC_11_14") (pintype "no_connect"))
    )
    (net (code "112") (name "unconnected-(U8-DNC_12-Pad15)") (class "Default")
      (node (ref "U8") (pin "15") (pinfunction "DNC_12_15") (pintype "no_connect"))
    )
    (net (code "113") (name "unconnected-(U8-DNC_13-Pad16)") (class "Default")
      (node (ref "U8") (pin "16") (pinfunction "DNC_13_16") (pintype "no_connect"))
    )
    (net (code "114") (name "unconnected-(U8-DNC_14-Pad17)") (class "Default")
      (node (ref "U8") (pin "17") (pinfunction "DNC_14_17") (pintype "no_connect"))
    )
    (net (code "115") (name "unconnected-(U9-NC-Pad4)") (class "Default")
      (node (ref "U9") (pin "4") (pinfunction "NC_4") (pintype "passive"))
    )
    (net (code "116") (name "unconnected-(U9-NC_2-Pad3)") (class "Default")
      (node (ref "U9") (pin "3") (pinfunction "NC_2_3") (pintype "passive"))
    )
  )
)
